# Power_LED_Circuit.net
KiCad netlist of a schematic drawn in Altium Designer
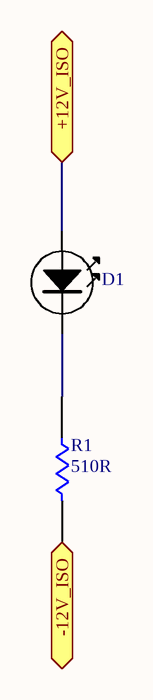
[diagram p0: Power LED Circuit.SchDoc]

(export (version "E")
  (design (tool "Eeschema 10.0.6"))
  (components
    (comp (ref "D1")
      (value "LED Diode_Green")
      (footprint "D0805")
      (libsource (lib "ucc28180-V04") (part "LED Diode_Green"))
    )
    (comp (ref "R1")
      (value "ERJ-PB6B5100V")
      (footprint "RES0805_New")
      (description "RES SMD 510 OHM 0.1% 1/4W 0805")
      (fields
        (field (name "MANUFACTURER") "Panasonic")
        (field (name "TOLERANCE") "0.1%")
        (field (name "RESISTANCE") "510R")
      )
      (libsource (lib "ucc28180-V04") (part "ERJ-PB6B5100V"))
    )
  )
  (nets
    (net (code "1") (name "/+12V_ISO") (class "Default") (node (ref "D1") (pin "2") (pintype "passive")))
    (net (code "2") (name "/-12V_ISO") (class "Default")
      (node (ref "R1") (pin "2") (pinfunction "2_2") (pintype "passive"))
    )
    (net (code "3") (name "Net-(D1-Pad1)") (class "Default")
      (node (ref "D1") (pin "1") (pintype "passive"))
      (node (ref "R1") (pin "1") (pinfunction "1_1") (pintype "passive"))
    )
  )
)
